# racket.net
KiCad netlist of a schematic drawn in EAGLE
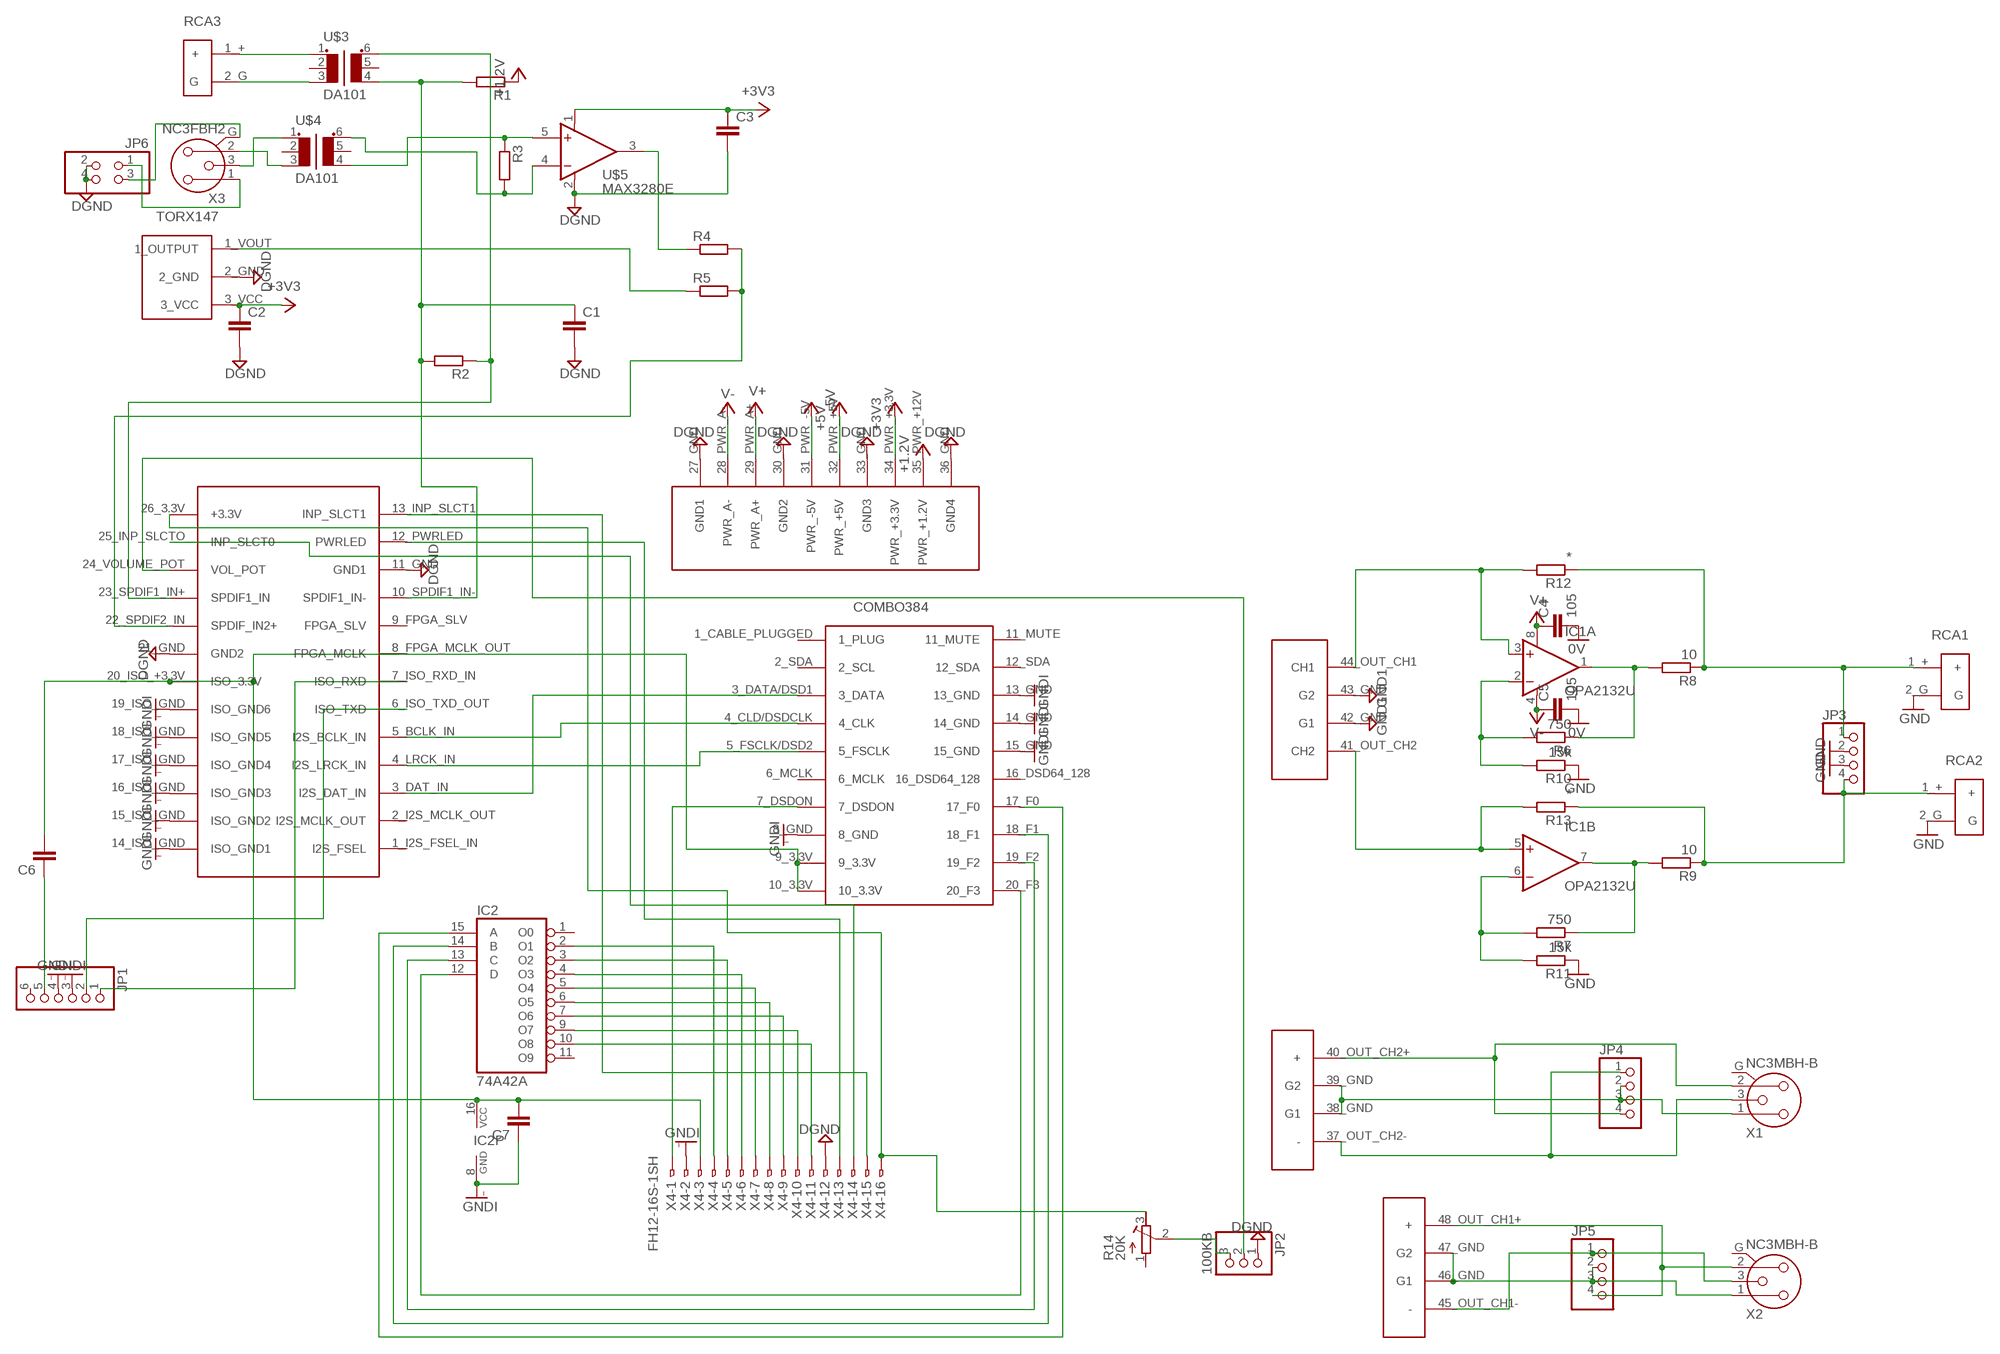
[diagram p0: schematic, sheet 1]

(export (version "E")
  (design (tool "Eeschema 10.0.6"))
  (components
    (comp (ref "C1")
      (value "C-EUC1206K")
      (footprint "eagle-import:C1206K")
      (libsource (lib "eagle-import") (part "C-EUC1206K"))
    )
    (comp (ref "C2")
      (value "C-EUC1206K")
      (footprint "eagle-import:C1206K")
      (libsource (lib "eagle-import") (part "C-EUC1206K"))
    )
    (comp (ref "C3")
      (value "C-EUC1206K")
      (footprint "eagle-import:C1206K")
      (libsource (lib "eagle-import") (part "C-EUC1206K"))
    )
    (comp (ref "C4")
      (value "105")
      (footprint "eagle-import:C1206K")
      (libsource (lib "eagle-import") (part "C-EUC1206K"))
    )
    (comp (ref "C5")
      (value "105")
      (footprint "eagle-import:C1206K")
      (libsource (lib "eagle-import") (part "C-EUC1206K"))
    )
    (comp (ref "C6")
      (value "C-EUC1206K")
      (footprint "eagle-import:C1206K")
      (libsource (lib "eagle-import") (part "C-EUC1206K"))
    )
    (comp (ref "C7")
      (value "C-EUC1206K")
      (footprint "eagle-import:C1206K")
      (libsource (lib "eagle-import") (part "C-EUC1206K"))
    )
    (comp (ref "IC1")
      (value "OPA2132U")
      (footprint "eagle-import:SO08")
      (fields (field (name "MF") "TEXAS INSTRUMENTS"))
      (libsource (lib "eagle-import") (part "OPA2132U"))
    )
    (comp (ref "IC2")
      (value "74A42A")
      (footprint "eagle-import:SO16NS")
      (libsource (lib "eagle-import") (part "7442AA"))
    )
    (comp (ref "JP1")
      (value "PINHD-1X6")
      (footprint "eagle-import:1X06")
      (libsource (lib "eagle-import") (part "PINHD-1X6"))
    )
    (comp (ref "JP2")
      (value "100KB")
      (footprint "eagle-import:1X03")
      (libsource (lib "eagle-import") (part "PINHD-1X3"))
    )
    (comp (ref "JP3")
      (value "PINHD-1X4")
      (footprint "eagle-import:1X04")
      (libsource (lib "eagle-import") (part "PINHD-1X4"))
    )
    (comp (ref "JP4")
      (value "PINHD-1X4")
      (footprint "eagle-import:1X04")
      (libsource (lib "eagle-import") (part "PINHD-1X4"))
    )
    (comp (ref "JP5")
      (value "PINHD-1X4")
      (footprint "eagle-import:1X04")
      (libsource (lib "eagle-import") (part "PINHD-1X4"))
    )
    (comp (ref "JP6")
      (value "PINHD-2X2")
      (footprint "eagle-import:2X02")
      (libsource (lib "eagle-import") (part "PINHD-2X2"))
    )
    (comp (ref "R1")
      (value "R-EU_M1206")
      (footprint "eagle-import:M1206")
      (libsource (lib "eagle-import") (part "R-EU_M1206"))
    )
    (comp (ref "R2")
      (value "R-EU_M1206")
      (footprint "eagle-import:M1206")
      (libsource (lib "eagle-import") (part "R-EU_M1206"))
    )
    (comp (ref "R3")
      (value "R-EU_M1206")
      (footprint "eagle-import:M1206")
      (libsource (lib "eagle-import") (part "R-EU_M1206"))
    )
    (comp (ref "R4")
      (value "R-EU_M1206")
      (footprint "eagle-import:M1206")
      (libsource (lib "eagle-import") (part "R-EU_M1206"))
    )
    (comp (ref "R5")
      (value "R-EU_M1206")
      (footprint "eagle-import:M1206")
      (libsource (lib "eagle-import") (part "R-EU_M1206"))
    )
    (comp (ref "R6")
      (value "750")
      (footprint "eagle-import:M1206")
      (libsource (lib "eagle-import") (part "R-EU_M1206"))
    )
    (comp (ref "R7")
      (value "750")
      (footprint "eagle-import:M1206")
      (libsource (lib "eagle-import") (part "R-EU_M1206"))
    )
    (comp (ref "R8")
      (value "10")
      (footprint "eagle-import:M1206")
      (libsource (lib "eagle-import") (part "R-EU_M1206"))
    )
    (comp (ref "R9")
      (value "10")
      (footprint "eagle-import:M1206")
      (libsource (lib "eagle-import") (part "R-EU_M1206"))
    )
    (comp (ref "R10")
      (value "15k")
      (footprint "eagle-import:M1206")
      (libsource (lib "eagle-import") (part "R-EU_M1206"))
    )
    (comp (ref "R11")
      (value "15k")
      (footprint "eagle-import:M1206")
      (libsource (lib "eagle-import") (part "R-EU_M1206"))
    )
    (comp (ref "R12")
      (value "*")
      (footprint "eagle-import:M1206")
      (libsource (lib "eagle-import") (part "R-EU_M1206"))
    )
    (comp (ref "R13")
      (value "*")
      (footprint "eagle-import:M1206")
      (libsource (lib "eagle-import") (part "R-EU_M1206"))
    )
    (comp (ref "R14")
      (value "20K")
      (footprint "eagle-import:RTRIM64W")
      (libsource (lib "eagle-import") (part "R-TRIMM64W"))
    )
    (comp (ref "RCA1")
      (value "RCA")
      (footprint "eagle-import:RCA")
      (libsource (lib "eagle-import") (part "RCA"))
    )
    (comp (ref "RCA2")
      (value "RCA")
      (footprint "eagle-import:RCA")
      (libsource (lib "eagle-import") (part "RCA"))
    )
    (comp (ref "RCA3")
      (value "RCA")
      (footprint "eagle-import:RCA")
      (libsource (lib "eagle-import") (part "RCA"))
    )
    (comp (ref "U$1")
      (value "TORX178")
      (footprint "eagle-import:TORX178B")
      (libsource (lib "eagle-import") (part "TORX178"))
    )
    (comp (ref "U$2")
      (value "DAM1021")
      (footprint "eagle-import:DAM1021")
      (libsource (lib "eagle-import") (part "DAM1021"))
    )
    (comp (ref "U$3")
      (value "DA101")
      (footprint "eagle-import:DAC101")
      (libsource (lib "eagle-import") (part "DA101"))
    )
    (comp (ref "U$4")
      (value "DA101")
      (footprint "eagle-import:DAC101")
      (libsource (lib "eagle-import") (part "DA101"))
    )
    (comp (ref "U$5")
      (value "MAX3280E")
      (footprint "eagle-import:SOT23-5L")
      (libsource (lib "eagle-import") (part "MAX3280E"))
    )
    (comp (ref "USB1")
      (value "COMBO384")
      (footprint "eagle-import:COMBO384_B")
      (libsource (lib "eagle-import") (part "COMBO384"))
    )
    (comp (ref "X1")
      (value "NC3MBH-B")
      (footprint "eagle-import:NC3MBH-B")
      (libsource (lib "eagle-import") (part "NC3MBH-B"))
    )
    (comp (ref "X2")
      (value "NC3MBH-B")
      (footprint "eagle-import:NC3MBH-B")
      (libsource (lib "eagle-import") (part "NC3MBH-B"))
    )
    (comp (ref "X3")
      (value "NC3FBH2")
      (footprint "eagle-import:NC3FBH2")
      (libsource (lib "eagle-import") (part "NC3FBH2"))
    )
    (comp (ref "X4")
      (value "FH12-16S-1SH")
      (footprint "eagle-import:FH12-16S-1SH")
      (libsource (lib "eagle-import") (part "FH12-16S-1SH"))
    )
  )
  (nets
    (net (code "1") (name "+1.2V") (class "Default")
      (node (ref "R1") (pin "1") (pinfunction "1_1") (pintype "passive"))
      (node (ref "U$2") (pin "35_PWR_+12V") (pinfunction "PWR_+1.2V_35_PWR_+12V") (pintype "bidirectional"))
    )
    (net (code "2") (name "+3V3") (class "Default")
      (node (ref "C2") (pin "1") (pinfunction "1_1") (pintype "passive"))
      (node (ref "C3") (pin "1") (pinfunction "1_1") (pintype "passive"))
      (node (ref "U$1") (pin "3_VCC") (pinfunction "3_VCC_3_VCC") (pintype "bidirectional"))
      (node (ref "U$2") (pin "34_PWR_+3.3V") (pinfunction "PWR_+3.3V_34_PWR_+3.3V") (pintype "bidirectional"))
      (node (ref "U$5") (pin "1") (pinfunction "V+_1") (pintype "power_in"))
    )
    (net (code "3") (name "+5V") (class "Default")
      (node (ref "U$2") (pin "32_PWR_+5V") (pinfunction "PWR_+5V_32_PWR_+5V") (pintype "bidirectional"))
    )
    (net (code "4") (name "-5V") (class "Default")
      (node (ref "U$2") (pin "31_PWR_-5V") (pinfunction "PWR_-5V_31_PWR_-5V") (pintype "bidirectional"))
    )
    (net (code "5") (name "0V") (class "Default")
      (node (ref "C4") (pin "2") (pinfunction "2_2") (pintype "passive"))
      (node (ref "C5") (pin "2") (pinfunction "2_2") (pintype "passive"))
    )
    (net (code "6") (name "DGND") (class "Default")
      (node (ref "C1") (pin "2") (pinfunction "2_2") (pintype "passive"))
      (node (ref "C2") (pin "2") (pinfunction "2_2") (pintype "passive"))
      (node (ref "C3") (pin "2") (pinfunction "2_2") (pintype "passive"))
      (node (ref "JP2") (pin "1") (pinfunction "1_1") (pintype "passive"))
      (node (ref "JP6") (pin "2") (pinfunction "2_2") (pintype "passive"))
      (node (ref "JP6") (pin "4") (pinfunction "4_4") (pintype "passive"))
      (node (ref "U$1") (pin "2_GND") (pinfunction "2_GND_2_GND") (pintype "bidirectional"))
      (node (ref "U$2") (pin "11_GND") (pinfunction "GND1_11_GND") (pintype "bidirectional"))
      (node (ref "U$2") (pin "21_GND") (pinfunction "GND2_21_GND") (pintype "bidirectional"))
      (node (ref "U$2") (pin "27_GND") (pinfunction "GND1_27_GND") (pintype "bidirectional"))
      (node (ref "U$2") (pin "30_GND") (pinfunction "GND2_30_GND") (pintype "bidirectional"))
      (node (ref "U$2") (pin "33_GND") (pinfunction "GND3_33_GND") (pintype "bidirectional"))
      (node (ref "U$2") (pin "36_GND") (pinfunction "GND4_36_GND") (pintype "bidirectional"))
      (node (ref "U$5") (pin "2") (pinfunction "V-_2") (pintype "power_in"))
      (node (ref "X4") (pin "12") (pinfunction "1_12") (pintype "passive"))
    )
    (net (code "7") (name "GND") (class "Default")
      (node (ref "JP3") (pin "2") (pinfunction "2_2") (pintype "passive"))
      (node (ref "JP3") (pin "3") (pinfunction "3_3") (pintype "passive"))
      (node (ref "R10") (pin "1") (pinfunction "1_1") (pintype "passive"))
      (node (ref "R11") (pin "1") (pinfunction "1_1") (pintype "passive"))
      (node (ref "RCA1") (pin "2_G") (pinfunction "G_2_G") (pintype "bidirectional"))
      (node (ref "RCA2") (pin "2_G") (pinfunction "G_2_G") (pintype "bidirectional"))
    )
    (net (code "8") (name "GND1") (class "Default")
      (node (ref "U$2") (pin "42_GND") (pinfunction "G1_42_GND") (pintype "bidirectional"))
      (node (ref "U$2") (pin "43_GND") (pinfunction "G2_43_GND") (pintype "bidirectional"))
    )
    (net (code "9") (name "GNDI") (class "Default")
      (node (ref "C7") (pin "1") (pinfunction "1_1") (pintype "passive"))
      (node (ref "IC2") (pin "8") (pinfunction "GND_8") (pintype "power_in"))
      (node (ref "JP1") (pin "3") (pinfunction "3_3") (pintype "passive"))
      (node (ref "JP1") (pin "4") (pinfunction "4_4") (pintype "passive"))
      (node (ref "U$2") (pin "14_ISO_GND") (pinfunction "ISO_GND1_14_ISO_GND") (pintype "bidirectional"))
      (node (ref "U$2") (pin "15_ISO_GND") (pinfunction "ISO_GND2_15_ISO_GND") (pintype "bidirectional"))
      (node (ref "U$2") (pin "16_ISO_GND") (pinfunction "ISO_GND3_16_ISO_GND") (pintype "bidirectional"))
      (node (ref "U$2") (pin "17_ISO_GND") (pinfunction "ISO_GND4_17_ISO_GND") (pintype "bidirectional"))
      (node (ref "U$2") (pin "18_ISO_GND") (pinfunction "ISO_GND5_18_ISO_GND") (pintype "bidirectional"))
      (node (ref "U$2") (pin "19_ISO_GND") (pinfunction "ISO_GND6_19_ISO_GND") (pintype "bidirectional"))
      (node (ref "USB1") (pin "13_GND") (pinfunction "13_GND_13_GND") (pintype "bidirectional"))
      (node (ref "USB1") (pin "14_GND") (pinfunction "14_GND_14_GND") (pintype "bidirectional"))
      (node (ref "USB1") (pin "15_GND") (pinfunction "15_GND_15_GND") (pintype "bidirectional"))
      (node (ref "USB1") (pin "8_GND") (pinfunction "8_GND_8_GND") (pintype "bidirectional"))
      (node (ref "X4") (pin "2") (pinfunction "1_2") (pintype "passive"))
    )
    (net (code "10") (name "Net-(C6-Pad1)") (class "Default")
      (node (ref "C6") (pin "1") (pinfunction "1_1") (pintype "passive"))
      (node (ref "JP1") (pin "5") (pinfunction "5_5") (pintype "passive"))
    )
    (net (code "11") (name "Net-(IC1A-+IN)") (class "Default")
      (node (ref "IC1") (pin "3") (pinfunction "+IN_3") (pintype "input"))
      (node (ref "R12") (pin "2") (pinfunction "2_2") (pintype "passive"))
      (node (ref "U$2") (pin "44_OUT_CH1") (pinfunction "CH1_44_OUT_CH1") (pintype "bidirectional"))
    )
    (net (code "12") (name "Net-(IC1A--IN)") (class "Default")
      (node (ref "IC1") (pin "2") (pinfunction "-IN_2") (pintype "input"))
      (node (ref "R10") (pin "2") (pinfunction "2_2") (pintype "passive"))
      (node (ref "R6") (pin "2") (pinfunction "2_2") (pintype "passive"))
    )
    (net (code "13") (name "Net-(IC1A-OUT)") (class "Default")
      (node (ref "IC1") (pin "1") (pinfunction "OUT_1") (pintype "output"))
      (node (ref "R6") (pin "1") (pinfunction "1_1") (pintype "passive"))
      (node (ref "R8") (pin "2") (pinfunction "2_2") (pintype "passive"))
    )
    (net (code "14") (name "Net-(IC1B-+IN)") (class "Default")
      (node (ref "IC1") (pin "5") (pinfunction "+IN_5") (pintype "input"))
      (node (ref "R13") (pin "2") (pinfunction "2_2") (pintype "passive"))
      (node (ref "U$2") (pin "41_OUT_CH2") (pinfunction "CH2_41_OUT_CH2") (pintype "bidirectional"))
    )
    (net (code "15") (name "Net-(IC1B--IN)") (class "Default")
      (node (ref "IC1") (pin "6") (pinfunction "-IN_6") (pintype "input"))
      (node (ref "R11") (pin "2") (pinfunction "2_2") (pintype "passive"))
      (node (ref "R7") (pin "2") (pinfunction "2_2") (pintype "passive"))
    )
    (net (code "16") (name "Net-(IC1B-OUT)") (class "Default")
      (node (ref "IC1") (pin "7") (pinfunction "OUT_7") (pintype "output"))
      (node (ref "R7") (pin "1") (pinfunction "1_1") (pintype "passive"))
      (node (ref "R9") (pin "2") (pinfunction "2_2") (pintype "passive"))
    )
    (net (code "17") (name "Net-(IC2A-A)") (class "Default")
      (node (ref "IC2") (pin "15") (pinfunction "A_15") (pintype "input"))
      (node (ref "USB1") (pin "17_F0") (pinfunction "17_F0_17_F0") (pintype "bidirectional"))
    )
    (net (code "18") (name "Net-(IC2A-B)") (class "Default")
      (node (ref "IC2") (pin "14") (pinfunction "B_14") (pintype "input"))
      (node (ref "USB1") (pin "18_F1") (pinfunction "18_F1_18_F1") (pintype "bidirectional"))
    )
    (net (code "19") (name "Net-(IC2A-C)") (class "Default")
      (node (ref "IC2") (pin "13") (pinfunction "C_13") (pintype "input"))
      (node (ref "USB1") (pin "19_F2") (pinfunction "19_F2_19_F2") (pintype "bidirectional"))
    )
    (net (code "20") (name "Net-(IC2A-D)") (class "Default")
      (node (ref "IC2") (pin "12") (pinfunction "D_12") (pintype "input"))
      (node (ref "USB1") (pin "20_F3") (pinfunction "20_F3_20_F3") (pintype "bidirectional"))
    )
    (net (code "21") (name "Net-(IC2A-O1)") (class "Default")
      (node (ref "IC2") (pin "2") (pinfunction "O1_2") (pintype "output"))
      (node (ref "X4") (pin "4") (pinfunction "1_4") (pintype "passive"))
    )
    (net (code "22") (name "Net-(IC2A-O2)") (class "Default")
      (node (ref "IC2") (pin "3") (pinfunction "O2_3") (pintype "output"))
      (node (ref "X4") (pin "5") (pinfunction "1_5") (pintype "passive"))
    )
    (net (code "23") (name "Net-(IC2A-O3)") (class "Default")
      (node (ref "IC2") (pin "4") (pinfunction "O3_4") (pintype "output"))
      (node (ref "X4") (pin "6") (pinfunction "1_6") (pintype "passive"))
    )
    (net (code "24") (name "Net-(IC2A-O4)") (class "Default")
      (node (ref "IC2") (pin "5") (pinfunction "O4_5") (pintype "output"))
      (node (ref "X4") (pin "7") (pinfunction "1_7") (pintype "passive"))
    )
    (net (code "25") (name "Net-(IC2A-O5)") (class "Default")
      (node (ref "IC2") (pin "6") (pinfunction "O5_6") (pintype "output"))
      (node (ref "X4") (pin "8") (pinfunction "1_8") (pintype "passive"))
    )
    (net (code "26") (name "Net-(IC2A-O6)") (class "Default")
      (node (ref "IC2") (pin "7") (pinfunction "O6_7") (pintype "output"))
      (node (ref "X4") (pin "9") (pinfunction "1_9") (pintype "passive"))
    )
    (net (code "27") (name "Net-(IC2A-O7)") (class "Default")
      (node (ref "IC2") (pin "9") (pinfunction "O7_9") (pintype "output"))
      (node (ref "X4") (pin "10") (pinfunction "1_10") (pintype "passive"))
    )
    (net (code "28") (name "Net-(IC2A-O8)") (class "Default")
      (node (ref "IC2") (pin "10") (pinfunction "O8_10") (pintype "output"))
      (node (ref "X4") (pin "11") (pinfunction "1_11") (pintype "passive"))
    )
    (net (code "29") (name "Net-(IC2B-VCC)") (class "Default")
      (node (ref "C6") (pin "2") (pinfunction "2_2") (pintype "passive"))
      (node (ref "C7") (pin "2") (pinfunction "2_2") (pintype "passive"))
      (node (ref "IC2") (pin "16") (pinfunction "VCC_16") (pintype "power_in"))
      (node (ref "U$2") (pin "20_ISO_+3.3V") (pinfunction "ISO_3.3V_20_ISO_+3.3V") (pintype "bidirectional"))
      (node (ref "USB1") (pin "10_3.3V") (pinfunction "10_3.3V_10_3.3V") (pintype "bidirectional"))
      (node (ref "USB1") (pin "9_3.3V") (pinfunction "9_3.3V_9_3.3V") (pintype "bidirectional"))
      (node (ref "X4") (pin "3") (pinfunction "1_3") (pintype "passive"))
    )
    (net (code "30") (name "Net-(JP6-Pad1)") (class "Default")
      (node (ref "JP6") (pin "1") (pinfunction "1_1") (pintype "passive"))
      (node (ref "X3") (pin "1") (pinfunction "1_1") (pintype "passive"))
    )
    (net (code "31") (name "Net-(JP6-Pad3)") (class "Default")
      (node (ref "JP6") (pin "3") (pinfunction "3_3") (pintype "passive"))
      (node (ref "X3") (pin "G") (pinfunction "G_G") (pintype "passive"))
    )
    (net (code "32") (name "Net-(R14-E)") (class "Default")
      (node (ref "R14") (pin "3") (pinfunction "E_3") (pintype "passive"))
      (node (ref "U$2") (pin "26_3.3V") (pinfunction "+3.3V_26_3.3V") (pintype "bidirectional"))
      (node (ref "X4") (pin "16") (pinfunction "1_16") (pintype "passive"))
    )
    (net (code "33") (name "Net-(R14-S)") (class "Default")
      (node (ref "JP2") (pin "3") (pinfunction "3_3") (pintype "passive"))
      (node (ref "R14") (pin "2") (pinfunction "S_2") (pintype "passive"))
    )
    (net (code "34") (name "Net-(RCA1-+)") (class "Default")
      (node (ref "JP3") (pin "1") (pinfunction "1_1") (pintype "passive"))
      (node (ref "R12") (pin "1") (pinfunction "1_1") (pintype "passive"))
      (node (ref "R8") (pin "1") (pinfunction "1_1") (pintype "passive"))
      (node (ref "RCA1") (pin "1_+") (pinfunction "+_1_+") (pintype "bidirectional"))
    )
    (net (code "35") (name "Net-(RCA2-+)") (class "Default")
      (node (ref "JP3") (pin "4") (pinfunction "4_4") (pintype "passive"))
      (node (ref "R13") (pin "1") (pinfunction "1_1") (pintype "passive"))
      (node (ref "R9") (pin "1") (pinfunction "1_1") (pintype "passive"))
      (node (ref "RCA2") (pin "1_+") (pinfunction "+_1_+") (pintype "bidirectional"))
    )
    (net (code "36") (name "Net-(RCA3-+)") (class "Default")
      (node (ref "RCA3") (pin "1_+") (pinfunction "+_1_+") (pintype "bidirectional"))
      (node (ref "U$3") (pin "1") (pinfunction "1_1") (pintype "passive"))
    )
    (net (code "37") (name "Net-(RCA3-G)") (class "Default")
      (node (ref "RCA3") (pin "2_G") (pinfunction "G_2_G") (pintype "bidirectional"))
      (node (ref "U$3") (pin "3") (pinfunction "3_3") (pintype "passive"))
    )
    (net (code "38") (name "Net-(U$1-1_OUTPUT)") (class "Default")
      (node (ref "R5") (pin "1") (pinfunction "1_1") (pintype "passive"))
      (node (ref "U$1") (pin "1_VOUT") (pinfunction "1_OUTPUT_1_VOUT") (pintype "bidirectional"))
    )
    (net (code "39") (name "Net-(U$2A-I2S_BCLK_IN)") (class "Default")
      (node (ref "U$2") (pin "5_BCLK_IN") (pinfunction "I2S_BCLK_IN_5_BCLK_IN") (pintype "bidirectional"))
      (node (ref "USB1") (pin "4_CLD/DSDCLK") (pinfunction "4_CLK_4_CLD/DSDCLK") (pintype "bidirectional"))
    )
    (net (code "40") (name "Net-(U$2A-I2S_DAT_IN)") (class "Default")
      (node (ref "U$2") (pin "3_DAT_IN") (pinfunction "I2S_DAT_IN_3_DAT_IN") (pintype "bidirectional"))
      (node (ref "USB1") (pin "3_DATA/DSD1") (pinfunction "3_DATA_3_DATA/DSD1") (pintype "bidirectional"))
    )
    (net (code "41") (name "Net-(U$2A-I2S_LRCK_IN)") (class "Default")
      (node (ref "U$2") (pin "4_LRCK_IN") (pinfunction "I2S_LRCK_IN_4_LRCK_IN") (pintype "bidirectional"))
      (node (ref "USB1") (pin "5_FSCLK/DSD2") (pinfunction "5_FSCLK_5_FSCLK/DSD2") (pintype "bidirectional"))
    )
    (net (code "42") (name "Net-(U$2A-INP_SLCT0)") (class "Default")
      (node (ref "U$2") (pin "25_INP_SLCTO") (pinfunction "INP_SLCT0_25_INP_SLCTO") (pintype "bidirectional"))
      (node (ref "X4") (pin "14") (pinfunction "1_14") (pintype "passive"))
    )
    (net (code "43") (name "Net-(U$2A-INP_SLCT1)") (class "Default")
      (node (ref "U$2") (pin "13_INP_SLCT1") (pinfunction "INP_SLCT1_13_INP_SLCT1") (pintype "bidirectional"))
      (node (ref "X4") (pin "15") (pinfunction "1_15") (pintype "passive"))
    )
    (net (code "44") (name "Net-(U$2A-ISO_RXD)") (class "Default")
      (node (ref "JP1") (pin "1") (pinfunction "1_1") (pintype "passive"))
      (node (ref "U$2") (pin "7_ISO_RXD_IN") (pinfunction "ISO_RXD_7_ISO_RXD_IN") (pintype "bidirectional"))
    )
    (net (code "45") (name "Net-(U$2A-ISO_TXD)") (class "Default")
      (node (ref "JP1") (pin "2") (pinfunction "2_2") (pintype "passive"))
      (node (ref "U$2") (pin "6_ISO_TXD_OUT") (pinfunction "ISO_TXD_6_ISO_TXD_OUT") (pintype "bidirectional"))
    )
    (net (code "46") (name "Net-(U$2A-PWRLED)") (class "Default")
      (node (ref "U$2") (pin "12_PWRLED") (pinfunction "PWRLED_12_PWRLED") (pintype "bidirectional"))
      (node (ref "X4") (pin "13") (pinfunction "1_13") (pintype "passive"))
    )
    (net (code "47") (name "Net-(U$2A-SPDIF1_IN)") (class "Default")
      (node (ref "R2") (pin "1") (pinfunction "1_1") (pintype "passive"))
      (node (ref "U$2") (pin "23_SPDIF1_IN+") (pinfunction "SPDIF1_IN_23_SPDIF1_IN+") (pintype "bidirectional"))
      (node (ref "U$3") (pin "6") (pinfunction "4_6") (pintype "passive"))
    )
    (net (code "48") (name "Net-(U$2A-SPDIF1_IN-)") (class "Default")
      (node (ref "C1") (pin "1") (pinfunction "1_1") (pintype "passive"))
      (node (ref "R1") (pin "2") (pinfunction "2_2") (pintype "passive"))
      (node (ref "R2") (pin "2") (pinfunction "2_2") (pintype "passive"))
      (node (ref "U$2") (pin "10_SPDIF1_IN-") (pinfunction "SPDIF1_IN-_10_SPDIF1_IN-") (pintype "bidirectional"))
      (node (ref "U$3") (pin "4") (pinfunction "6_4") (pintype "passive"))
    )
    (net (code "49") (name "Net-(U$2A-SPDIF_IN2+)") (class "Default")
      (node (ref "R4") (pin "2") (pinfunction "2_2") (pintype "passive"))
      (node (ref "R5") (pin "2") (pinfunction "2_2") (pintype "passive"))
      (node (ref "U$2") (pin "22_SPDIF2_IN") (pinfunction "SPDIF_IN2+_22_SPDIF2_IN") (pintype "bidirectional"))
    )
    (net (code "50") (name "Net-(U$2A-VOL_POT)") (class "Default")
      (node (ref "JP2") (pin "2") (pinfunction "2_2") (pintype "passive"))
      (node (ref "U$2") (pin "24_VOLUME_POT") (pinfunction "VOL_POT_24_VOLUME_POT") (pintype "bidirectional"))
    )
    (net (code "51") (name "Net-(U$2C-+)") (class "Default")
      (node (ref "JP4") (pin "4") (pinfunction "4_4") (pintype "passive"))
      (node (ref "U$2") (pin "40_OUT_CH2+") (pinfunction "+_40_OUT_CH2+") (pintype "bidirectional"))
      (node (ref "X1") (pin "2") (pinfunction "2_2") (pintype "passive"))
    )
    (net (code "52") (name "Net-(U$2C--)") (class "Default")
      (node (ref "JP4") (pin "1") (pinfunction "1_1") (pintype "passive"))
      (node (ref "U$2") (pin "37_OUT_CH2-") (pinfunction "-_37_OUT_CH2-") (pintype "bidirectional"))
      (node (ref "X1") (pin "3") (pinfunction "3_3") (pintype "passive"))
    )
    (net (code "53") (name "Net-(U$2C-G1)") (class "Default")
      (node (ref "JP4") (pin "2") (pinfunction "2_2") (pintype "passive"))
      (node (ref "JP4") (pin "3") (pinfunction "3_3") (pintype "passive"))
      (node (ref "U$2") (pin "38_GND") (pinfunction "G1_38_GND") (pintype "bidirectional"))
      (node (ref "U$2") (pin "39_GND") (pinfunction "G2_39_GND") (pintype "bidirectional"))
      (node (ref "X1") (pin "1") (pinfunction "1_1") (pintype "passive"))
    )
    (net (code "54") (name "Net-(U$2E-+)") (class "Default")
      (node (ref "JP5") (pin "4") (pinfunction "4_4") (pintype "passive"))
      (node (ref "U$2") (pin "48_OUT_CH1+") (pinfunction "+_48_OUT_CH1+") (pintype "bidirectional"))
      (node (ref "X2") (pin "2") (pinfunction "2_2") (pintype "passive"))
    )
    (net (code "55") (name "Net-(U$2E--)") (class "Default")
      (node (ref "JP5") (pin "1") (pinfunction "1_1") (pintype "passive"))
      (node (ref "U$2") (pin "45_OUT_CH1-") (pinfunction "-_45_OUT_CH1-") (pintype "bidirectional"))
      (node (ref "X2") (pin "3") (pinfunction "3_3") (pintype "passive"))
    )
    (net (code "56") (name "Net-(U$2E-G1)") (class "Default")
      (node (ref "JP5") (pin "2") (pinfunction "2_2") (pintype "passive"))
      (node (ref "JP5") (pin "3") (pinfunction "3_3") (pintype "passive"))
      (node (ref "U$2") (pin "46_GND") (pinfunction "G1_46_GND") (pintype "bidirectional"))
      (node (ref "U$2") (pin "47_GND") (pinfunction "G2_47_GND") (pintype "bidirectional"))
      (node (ref "X2") (pin "1") (pinfunction "1_1") (pintype "passive"))
    )
    (net (code "57") (name "Net-(U$4-4)") (class "Default")
      (node (ref "R3") (pin "2") (pinfunction "2_2") (pintype "passive"))
      (node (ref "U$4") (pin "6") (pinfunction "4_6") (pintype "passive"))
      (node (ref "U$5") (pin "4") (pinfunction "-IN_4") (pintype "input"))
    )
    (net (code "58") (name "Net-(U$4-6)") (class "Default")
      (node (ref "R3") (pin "1") (pinfunction "1_1") (pintype "passive"))
      (node (ref "U$4") (pin "4") (pinfunction "6_4") (pintype "passive"))
      (node (ref "U$5") (pin "5") (pinfunction "+IN_5") (pintype "input"))
    )
    (net (code "59") (name "Net-(U$4-Pad1)") (class "Default")
      (node (ref "U$4") (pin "1") (pinfunction "1_1") (pintype "passive"))
      (node (ref "X3") (pin "3") (pinfunction "3_3") (pintype "passive"))
    )
    (net (code "60") (name "Net-(U$4-Pad3)") (class "Default")
      (node (ref "U$4") (pin "3") (pinfunction "3_3") (pintype "passive"))
      (node (ref "X3") (pin "2") (pinfunction "2_2") (pintype "passive"))
    )
    (net (code "61") (name "Net-(U$5-OUT)") (class "Default")
      (node (ref "R4") (pin "1") (pinfunction "1_1") (pintype "passive"))
      (node (ref "U$5") (pin "3") (pinfunction "OUT_3") (pintype "output"))
    )
    (net (code "62") (name "Net-(USB1-Pad7_DSDON)") (class "Default")
      (node (ref "USB1") (pin "7_DSDON") (pinfunction "7_DSDON_7_DSDON") (pintype "bidirectional"))
      (node (ref "X4") (pin "1") (pinfunction "1_1") (pintype "passive"))
    )
    (net (code "63") (name "V+") (class "Default")
      (node (ref "C4") (pin "1") (pinfunction "1_1") (pintype "passive"))
      (node (ref "IC1") (pin "8") (pinfunction "V+_8") (pintype "power_in"))
      (node (ref "U$2") (pin "29_PWR_A+") (pinfunction "PWR_A+_29_PWR_A+") (pintype "bidirectional"))
    )
    (net (code "64") (name "V-") (class "Default")
      (node (ref "C5") (pin "1") (pinfunction "1_1") (pintype "passive"))
      (node (ref "IC1") (pin "4") (pinfunction "V-_4") (pintype "power_in"))
      (node (ref "U$2") (pin "28_PWR_A-") (pinfunction "PWR_A-_28_PWR_A-") (pintype "bidirectional"))
    )
    (net (code "65") (name "unconnected-(IC2A-O0-Pad1)") (class "Default")
      (node (ref "IC2") (pin "1") (pinfunction "O0_1") (pintype "output"))
    )
    (net (code "66") (name "unconnected-(IC2A-O9-Pad11)") (class "Default")
      (node (ref "IC2") (pin "11") (pinfunction "O9_11") (pintype "output"))
    )
    (net (code "67") (name "unconnected-(JP1-Pad6)") (class "Default")
      (node (ref "JP1") (pin "6") (pinfunction "6_6") (pintype "passive"))
    )
    (net (code "68") (name "unconnected-(R14-A-Pad1)") (class "Default")
      (node (ref "R14") (pin "1") (pinfunction "A_1") (pintype "passive"))
    )
    (net (code "69") (name "unconnected-(U$2A-FPGA_MCLK-Pad8_FPGA_MCLK_OUT)") (class "Default")
      (node (ref "U$2") (pin "8_FPGA_MCLK_OUT") (pinfunction "FPGA_MCLK_8_FPGA_MCLK_OUT") (pintype "bidirectional"))
    )
    (net (code "70") (name "unconnected-(U$2A-FPGA_SLV-Pad9_FPGA_SLV)") (class "Default")
      (node (ref "U$2") (pin "9_FPGA_SLV") (pinfunction "FPGA_SLV_9_FPGA_SLV") (pintype "bidirectional"))
    )
    (net (code "71") (name "unconnected-(U$2A-I2S_FSEL-Pad1_I2S_FSEL_IN)") (class "Default")
      (node (ref "U$2") (pin "1_I2S_FSEL_IN") (pinfunction "I2S_FSEL_1_I2S_FSEL_IN") (pintype "bidirectional"))
    )
    (net (code "72") (name "unconnected-(U$2A-I2S_MCLK_OUT-Pad2_I2S_MCLK_OUT)") (class "Default")
      (node (ref "U$2") (pin "2_I2S_MCLK_OUT") (pinfunction "I2S_MCLK_OUT_2_I2S_MCLK_OUT") (pintype "bidirectional"))
    )
    (net (code "73") (name "unconnected-(U$3-Pad2)") (class "Default")
      (node (ref "U$3") (pin "2") (pinfunction "2_2") (pintype "passive"))
    )
    (net (code "74") (name "unconnected-(U$3-Pad5)") (class "Default")
      (node (ref "U$3") (pin "5") (pinfunction "5_5") (pintype "passive"))
    )
    (net (code "75") (name "unconnected-(U$4-Pad2)") (class "Default")
      (node (ref "U$4") (pin "2") (pinfunction "2_2") (pintype "passive"))
    )
    (net (code "76") (name "unconnected-(U$4-Pad5)") (class "Default")
      (node (ref "U$4") (pin "5") (pinfunction "5_5") (pintype "passive"))
    )
    (net (code "77") (name "unconnected-(USB1-1_PLUG-Pad1_CABLE_PLUGGED)") (class "Default")
      (node (ref "USB1") (pin "1_CABLE_PLUGGED") (pinfunction "1_PLUG_1_CABLE_PLUGGED") (pintype "bidirectional"))
    )
    (net (code "78") (name "unconnected-(USB1-2_SCL-Pad2_SDA)") (class "Default")
      (node (ref "USB1") (pin "2_SDA") (pinfunction "2_SCL_2_SDA") (pintype "bidirectional"))
    )
    (net (code "79") (name "unconnected-(USB1-Pad6_MCLK)") (class "Default")
      (node (ref "USB1") (pin "6_MCLK") (pinfunction "6_MCLK_6_MCLK") (pintype "bidirectional"))
    )
    (net (code "80") (name "unconnected-(USB1-Pad11_MUTE)") (class "Default")
      (node (ref "USB1") (pin "11_MUTE") (pinfunction "11_MUTE_11_MUTE") (pintype "bidirectional"))
    )
    (net (code "81") (name "unconnected-(USB1-Pad12_SDA)") (class "Default")
      (node (ref "USB1") (pin "12_SDA") (pinfunction "12_SDA_12_SDA") (pintype "bidirectional"))
    )
    (net (code "82") (name "unconnected-(USB1-Pad16_DSD64_128)") (class "Default")
      (node (ref "USB1") (pin "16_DSD64_128") (pinfunction "16_DSD64_128_16_DSD64_128") (pintype "bidirectional"))
    )
    (net (code "83") (name "unconnected-(X1-PadG)") (class "Default")
      (node (ref "X1") (pin "G") (pinfunction "G_G") (pintype "passive"))
    )
    (net (code "84") (name "unconnected-(X2-PadG)") (class "Default")
      (node (ref "X2") (pin "G") (pinfunction "G_G") (pintype "passive"))
    )
  )
)
